# aasaver2_0.net
KiCad netlist of a schematic drawn in EAGLE
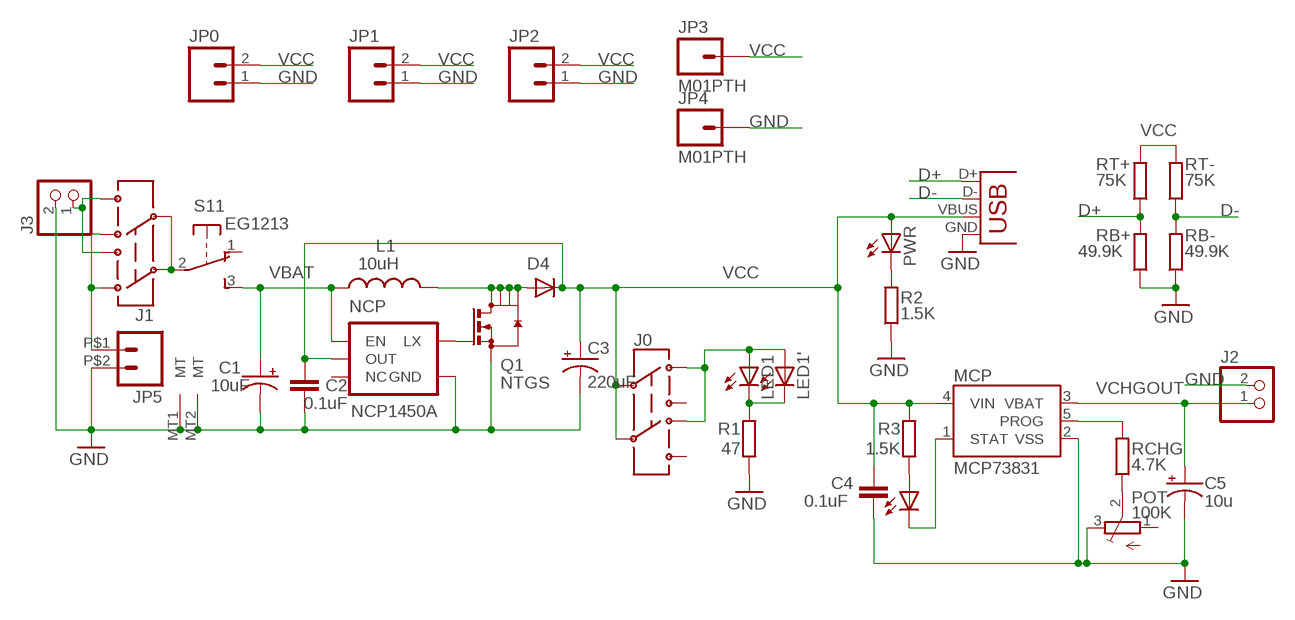
[diagram p0: schematic, sheet 1]

(export (version "E")
  (design (tool "Eeschema 10.0.6"))
  (components
    (comp (ref "C1")
      (value "10uF")
      (footprint "eagle-import:EIA3216")
      (libsource (lib "eagle-import") (part "CAP_POL1206"))
    )
    (comp (ref "C2")
      (value "0.1uF")
      (footprint "eagle-import:C0805")
      (libsource (lib "eagle-import") (part "C-EUC0805"))
    )
    (comp (ref "C3")
      (value "220uF")
      (footprint "eagle-import:EIA7343")
      (libsource (lib "eagle-import") (part "CAP_POL7343"))
    )
    (comp (ref "C4")
      (value "0.1uF")
      (footprint "eagle-import:C0805")
      (libsource (lib "eagle-import") (part "C-EUC0805"))
    )
    (comp (ref "C5")
      (value "10u")
      (footprint "eagle-import:EIA3216")
      (libsource (lib "eagle-import") (part "CAP_POL1206"))
    )
    (comp (ref "D4")
      (value "DIODEDO216")
      (footprint "eagle-import:DO216AA-DIODE")
      (libsource (lib "eagle-import") (part "DIODEDO216"))
    )
    (comp (ref "J0")
      (value "AYZ0202")
      (footprint "eagle-import:AYZ0202")
      (libsource (lib "eagle-import") (part "AYZ0202"))
    )
    (comp (ref "J1")
      (value "AYZ0202")
      (footprint "eagle-import:AYZ0202")
      (libsource (lib "eagle-import") (part "AYZ0202"))
    )
    (comp (ref "J2")
      (value "JST_2PIN-SMT-RA")
      (footprint "eagle-import:JST-PH-2-SMT-RA")
      (libsource (lib "eagle-import") (part "JST_2PIN-SMT-RA"))
    )
    (comp (ref "J3")
      (value "JST_2PIN-SMT-RA")
      (footprint "eagle-import:JST-PH-2-SMT-RA")
      (libsource (lib "eagle-import") (part "JST_2PIN-SMT-RA"))
    )
    (comp (ref "JP0")
      (value "M021X02_NO_SILK")
      (footprint "eagle-import:1X02_NO_SILK")
      (libsource (lib "eagle-import") (part "M021X02_NO_SILK"))
    )
    (comp (ref "JP1")
      (value "M021X02_NO_SILK")
      (footprint "eagle-import:1X02_NO_SILK")
      (libsource (lib "eagle-import") (part "M021X02_NO_SILK"))
    )
    (comp (ref "JP2")
      (value "M021X02_NO_SILK")
      (footprint "eagle-import:1X02_NO_SILK")
      (libsource (lib "eagle-import") (part "M021X02_NO_SILK"))
    )
    (comp (ref "JP3")
      (value "M01PTH")
      (footprint "eagle-import:1X01")
      (libsource (lib "eagle-import") (part "M01PTH"))
    )
    (comp (ref "JP4")
      (value "M01PTH")
      (footprint "eagle-import:1X01")
      (libsource (lib "eagle-import") (part "M01PTH"))
    )
    (comp (ref "JP5")
      (value "M02PTH2")
      (footprint "eagle-import:1X02_BIG")
      (libsource (lib "eagle-import") (part "M02PTH2"))
    )
    (comp (ref "L1")
      (value "10uH")
      (footprint "eagle-import:CR75")
      (libsource (lib "eagle-import") (part "INDUCTORCR75"))
    )
    (comp (ref "LED1")
      (value "LED3MM")
      (footprint "eagle-import:LED3MM")
      (libsource (lib "eagle-import") (part "LED3MM"))
    )
    (comp (ref "LED1'")
      (value "LED3MM")
      (footprint "eagle-import:LED3MM")
      (libsource (lib "eagle-import") (part "LED3MM"))
    )
    (comp (ref "LED3")
      (value "green")
      (footprint "eagle-import:CHIPLED_0805")
      (libsource (lib "eagle-import") (part "led_LEDCHIPLED_0805"))
    )
    (comp (ref "MCP")
      (value "MCP73831")
      (footprint "eagle-import:SOT23-5")
      (libsource (lib "eagle-import") (part "MCP73831"))
    )
    (comp (ref "NCP")
      (value "NCP1450A")
      (footprint "eagle-import:SOT23-5")
      (libsource (lib "eagle-import") (part "V_REG_NCP1400SOT23-5"))
    )
    (comp (ref "POT")
      (value "100K")
      (footprint "eagle-import:TC33X")
      (libsource (lib "eagle-import") (part "TRIMPOTTC33X"))
    )
    (comp (ref "PWR")
      (value "red")
      (footprint "eagle-import:CHIPLED_0805")
      (libsource (lib "eagle-import") (part "led_LEDCHIPLED_0805"))
    )
    (comp (ref "Q1")
      (value "NTGS")
      (footprint "eagle-import:SOT236")
      (libsource (lib "eagle-import") (part "NTGS3446"))
    )
    (comp (ref "R1")
      (value "47")
      (footprint "eagle-import:R0805")
      (libsource (lib "eagle-import") (part "R-EU_R0805"))
    )
    (comp (ref "R2")
      (value "1.5K")
      (footprint "eagle-import:R0805")
      (libsource (lib "eagle-import") (part "R-EU_R0805"))
    )
    (comp (ref "R3")
      (value "1.5K")
      (footprint "eagle-import:R0805")
      (libsource (lib "eagle-import") (part "R-EU_R0805"))
    )
    (comp (ref "RB+")
      (value "49.9K")
      (footprint "eagle-import:R0805")
      (libsource (lib "eagle-import") (part "R-EU_R0805"))
    )
    (comp (ref "RB-")
      (value "49.9K")
      (footprint "eagle-import:R0805")
      (libsource (lib "eagle-import") (part "R-EU_R0805"))
    )
    (comp (ref "RCHG")
      (value "4.7K")
      (footprint "eagle-import:R0805")
      (libsource (lib "eagle-import") (part "R-EU_R0805"))
    )
    (comp (ref "RT+")
      (value "75K")
      (footprint "eagle-import:R0805")
      (libsource (lib "eagle-import") (part "R-EU_R0805"))
    )
    (comp (ref "RT-")
      (value "75K")
      (footprint "eagle-import:R0805")
      (libsource (lib "eagle-import") (part "R-EU_R0805"))
    )
    (comp (ref "S1")
      (value "EG1213")
      (footprint "eagle-import:EG1213")
      (libsource (lib "eagle-import") (part "EG1213"))
    )
    (comp (ref "X1")
      (value "USB-A-S-FEMALE")
      (footprint "eagle-import:USB-A-S-FEMALE")
      (libsource (lib "eagle-import") (part "USB-A-S-FEMALE"))
    )
  )
  (nets
    (net (code "1") (name "/D+") (class "Default")
      (node (ref "RB+") (pin "2") (pinfunction "2_2") (pintype "passive"))
      (node (ref "RT+") (pin "1") (pinfunction "1_1") (pintype "passive"))
      (node (ref "X1") (pin "D+") (pinfunction "D+_D+") (pintype "bidirectional"))
    )
    (net (code "2") (name "/D-") (class "Default")
      (node (ref "RB-") (pin "2") (pinfunction "2_2") (pintype "passive"))
      (node (ref "RT-") (pin "1") (pinfunction "1_1") (pintype "passive"))
      (node (ref "X1") (pin "D-") (pinfunction "D-_D-") (pintype "bidirectional"))
    )
    (net (code "3") (name "/VBAT") (class "Default")
      (node (ref "C1") (pin "A") (pinfunction "+_A") (pintype "passive"))
      (node (ref "L1") (pin "P$1") (pinfunction "1_P$1") (pintype "passive"))
      (node (ref "NCP") (pin "1") (pinfunction "EN_1") (pintype "input"))
      (node (ref "S1") (pin "3") (pinfunction "S_3") (pintype "passive"))
    )
    (net (code "4") (name "/VCC") (class "Default")
      (node (ref "C2") (pin "2") (pinfunction "2_2") (pintype "passive"))
      (node (ref "C3") (pin "A") (pinfunction "+_A") (pintype "passive"))
      (node (ref "C4") (pin "1") (pinfunction "1_1") (pintype "passive"))
      (node (ref "D4") (pin "C") (pinfunction "C_C") (pintype "passive"))
      (node (ref "J0") (pin "2") (pinfunction "2_2") (pintype "bidirectional"))
      (node (ref "J0") (pin "5") (pinfunction "5_5") (pintype "bidirectional"))
      (node (ref "JP0") (pin "2") (pinfunction "2_2") (pintype "passive"))
      (node (ref "JP1") (pin "2") (pinfunction "2_2") (pintype "passive"))
      (node (ref "JP2") (pin "2") (pinfunction "2_2") (pintype "passive"))
      (node (ref "JP3") (pin "1") (pinfunction "1_1") (pintype "passive"))
      (node (ref "MCP") (pin "4") (pinfunction "VIN_4") (pintype "power_in"))
      (node (ref "NCP") (pin "2") (pinfunction "OUT_2") (pintype "passive"))
      (node (ref "PWR") (pin "A") (pinfunction "A_A") (pintype "passive"))
      (node (ref "R3") (pin "2") (pinfunction "2_2") (pintype "passive"))
      (node (ref "RT+") (pin "2") (pinfunction "2_2") (pintype "passive"))
      (node (ref "RT-") (pin "2") (pinfunction "2_2") (pintype "passive"))
      (node (ref "X1") (pin "VBUS") (pinfunction "VBUS_VBUS") (pintype "bidirectional"))
    )
    (net (code "5") (name "/VCHGOUT") (class "Default")
      (node (ref "C5") (pin "A") (pinfunction "+_A") (pintype "passive"))
      (node (ref "J2") (pin "1") (pinfunction "2_1") (pintype "passive"))
      (node (ref "MCP") (pin "3") (pinfunction "VBAT_3") (pintype "power_in"))
    )
    (net (code "6") (name "GND") (class "Default")
      (node (ref "C1") (pin "C") (pinfunction "-_C") (pintype "passive"))
      (node (ref "C2") (pin "1") (pinfunction "1_1") (pintype "passive"))
      (node (ref "C3") (pin "C") (pinfunction "-_C") (pintype "passive"))
      (node (ref "C4") (pin "2") (pinfunction "2_2") (pintype "passive"))
      (node (ref "C5") (pin "C") (pinfunction "-_C") (pintype "passive"))
      (node (ref "J2") (pin "2") (pinfunction "1_2") (pintype "passive"))
      (node (ref "J3") (pin "2") (pinfunction "1_2") (pintype "passive"))
      (node (ref "JP0") (pin "1") (pinfunction "1_1") (pintype "passive"))
      (node (ref "JP1") (pin "1") (pinfunction "1_1") (pintype "passive"))
      (node (ref "JP2") (pin "1") (pinfunction "1_1") (pintype "passive"))
      (node (ref "JP4") (pin "1") (pinfunction "1_1") (pintype "passive"))
      (node (ref "JP5") (pin "P$2") (pinfunction "2_P$2") (pintype "passive"))
      (node (ref "MCP") (pin "2") (pinfunction "VSS_2") (pintype "power_in"))
      (node (ref "NCP") (pin "4") (pinfunction "GND_4") (pintype "input"))
      (node (ref "POT") (pin "3") (pinfunction "E_3") (pintype "passive"))
      (node (ref "Q1") (pin "4") (pinfunction "S_4") (pintype "passive"))
      (node (ref "R1") (pin "1") (pinfunction "1_1") (pintype "passive"))
      (node (ref "R2") (pin "1") (pinfunction "1_1") (pintype "passive"))
      (node (ref "RB+") (pin "1") (pinfunction "1_1") (pintype "passive"))
      (node (ref "RB-") (pin "1") (pinfunction "1_1") (pintype "passive"))
      (node (ref "S1") (pin "MT1") (pinfunction "MT_MT1") (pintype "passive"))
      (node (ref "S1") (pin "MT2") (pinfunction "MT_MT2") (pintype "passive"))
      (node (ref "X1") (pin "GND") (pinfunction "GND_GND") (pintype "bidirectional"))
    )
    (net (code "7") (name "Net-(J0-1)") (class "Default")
      (node (ref "J0") (pin "3") (pinfunction "1_3") (pintype "bidirectional"))
      (node (ref "J0") (pin "6") (pinfunction "4_6") (pintype "bidirectional"))
      (node (ref "LED1") (pin "A") (pinfunction "A_A") (pintype "passive"))
      (node (ref "LED1'") (pin "A") (pinfunction "A_A") (pintype "passive"))
    )
    (net (code "8") (name "Net-(J1-1)") (class "Default")
      (node (ref "J1") (pin "3") (pinfunction "1_3") (pintype "bidirectional"))
      (node (ref "J1") (pin "6") (pinfunction "4_6") (pintype "bidirectional"))
      (node (ref "JP5") (pin "P$1") (pinfunction "1_P$1") (pintype "passive"))
    )
    (net (code "9") (name "Net-(J1-3)") (class "Default")
      (node (ref "J1") (pin "1") (pinfunction "3_1") (pintype "bidirectional"))
      (node (ref "J1") (pin "4") (pinfunction "6_4") (pintype "bidirectional"))
      (node (ref "J3") (pin "1") (pinfunction "2_1") (pintype "passive"))
    )
    (net (code "10") (name "Net-(L1-2)") (class "Default")
      (node (ref "D4") (pin "A") (pinfunction "A_A") (pintype "passive"))
      (node (ref "L1") (pin "P$2") (pinfunction "2_P$2") (pintype "passive"))
      (node (ref "Q1") (pin "1") (pinfunction "D_1") (pintype "passive"))
      (node (ref "Q1") (pin "2") (pinfunction "D1_2") (pintype "passive"))
      (node (ref "Q1") (pin "5") (pinfunction "D2_5") (pintype "passive"))
      (node (ref "Q1") (pin "6") (pinfunction "D3_6") (pintype "passive"))
    )
    (net (code "11") (name "Net-(LED1'-C)") (class "Default")
      (node (ref "LED1") (pin "K") (pinfunction "C_K") (pintype "passive"))
      (node (ref "LED1'") (pin "K") (pinfunction "C_K") (pintype "passive"))
      (node (ref "R1") (pin "2") (pinfunction "2_2") (pintype "passive"))
    )
    (net (code "12") (name "Net-(LED3-PadA)") (class "Default")
      (node (ref "LED3") (pin "A") (pinfunction "A_A") (pintype "passive"))
      (node (ref "R3") (pin "1") (pinfunction "1_1") (pintype "passive"))
    )
    (net (code "13") (name "Net-(MCP-PROG)") (class "Default")
      (node (ref "MCP") (pin "5") (pinfunction "PROG_5") (pintype "input"))
      (node (ref "RCHG") (pin "2") (pinfunction "2_2") (pintype "passive"))
    )
    (net (code "14") (name "Net-(MCP-STAT)") (class "Default")
      (node (ref "LED3") (pin "C") (pinfunction "C_C") (pintype "passive"))
      (node (ref "MCP") (pin "1") (pinfunction "STAT_1") (pintype "output"))
    )
    (net (code "15") (name "Net-(NCP-LX)") (class "Default")
      (node (ref "NCP") (pin "5") (pinfunction "LX_5") (pintype "input"))
      (node (ref "Q1") (pin "3") (pinfunction "G_3") (pintype "passive"))
    )
    (net (code "16") (name "Net-(POT-S)") (class "Default")
      (node (ref "POT") (pin "2") (pinfunction "S_2") (pintype "passive"))
      (node (ref "RCHG") (pin "1") (pinfunction "1_1") (pintype "passive"))
    )
    (net (code "17") (name "Net-(PWR-PadC)") (class "Default")
      (node (ref "PWR") (pin "C") (pinfunction "C_C") (pintype "passive"))
      (node (ref "R2") (pin "2") (pinfunction "2_2") (pintype "passive"))
    )
    (net (code "18") (name "Net-(S1A-P)") (class "Default")
      (node (ref "J1") (pin "2") (pinfunction "2_2") (pintype "bidirectional"))
      (node (ref "J1") (pin "5") (pinfunction "5_5") (pintype "bidirectional"))
      (node (ref "S1") (pin "2") (pinfunction "P_2") (pintype "passive"))
    )
    (net (code "19") (name "unconnected-(J0-3-Pad1)") (class "Default")
      (node (ref "J0") (pin "1") (pinfunction "3_1") (pintype "bidirectional"))
    )
    (net (code "20") (name "unconnected-(J0-6-Pad4)") (class "Default")
      (node (ref "J0") (pin "4") (pinfunction "6_4") (pintype "bidirectional"))
    )
    (net (code "21") (name "unconnected-(NCP-NC-Pad3)") (class "Default")
      (node (ref "NCP") (pin "3") (pinfunction "NC_3") (pintype "input"))
    )
    (net (code "22") (name "unconnected-(POT-A-Pad1)") (class "Default")
      (node (ref "POT") (pin "1") (pinfunction "A_1") (pintype "passive"))
    )
    (net (code "23") (name "unconnected-(S1A-O-Pad1)") (class "Default")
      (node (ref "S1") (pin "1") (pinfunction "O_1") (pintype "passive"))
    )
  )
)
